# leistungsmesser_4fach.net
KiCad netlist of a schematic drawn in EAGLE
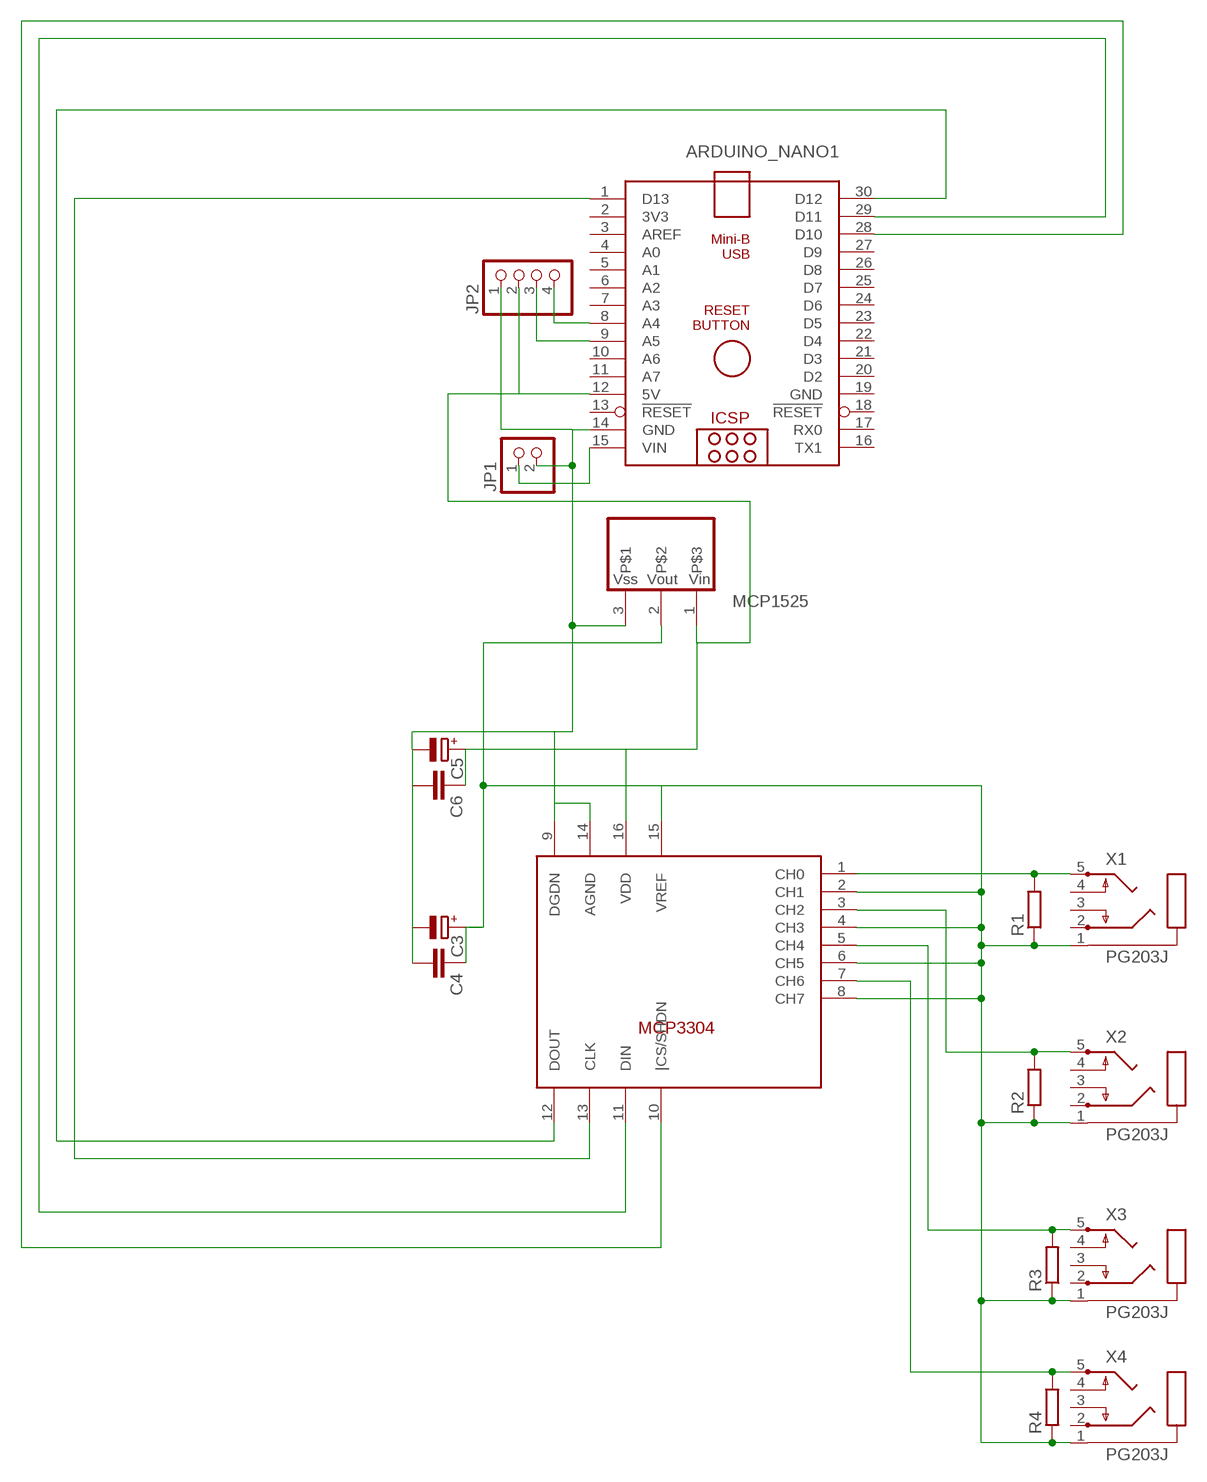
[diagram p0: schematic, sheet 1]

(export (version "E")
  (design (tool "Eeschema 10.0.6"))
  (components
    (comp (ref "ARDUINO_NANO1")
      (value "ARDUINO_NANO")
      (footprint "eagle-import:ARDUINO_NANO")
      (libsource (lib "eagle-import") (part "ARDUINO_NANO"))
    )
    (comp (ref "C3")
      (value "CPOL-EUE2,5-6E")
      (footprint "eagle-import:E2,5-6E")
      (libsource (lib "eagle-import") (part "CPOL-EUE2,5-6E"))
    )
    (comp (ref "C4")
      (value "C-EU025-024X044")
      (footprint "eagle-import:C025-024X044")
      (libsource (lib "eagle-import") (part "C-EU025-024X044"))
    )
    (comp (ref "C5")
      (value "CPOL-EUE2,5-6E")
      (footprint "eagle-import:E2,5-6E")
      (libsource (lib "eagle-import") (part "CPOL-EUE2,5-6E"))
    )
    (comp (ref "C6")
      (value "C-EU025-024X044")
      (footprint "eagle-import:C025-024X044")
      (libsource (lib "eagle-import") (part "C-EU025-024X044"))
    )
    (comp (ref "IC4")
      (value "MCP1525")
      (footprint "eagle-import:TO92-")
      (libsource (lib "eagle-import") (part "MCP1525"))
    )
    (comp (ref "JP1")
      (value "PINHD-1X2")
      (footprint "eagle-import:1X02")
      (libsource (lib "eagle-import") (part "PINHD-1X2"))
    )
    (comp (ref "JP2")
      (value "PINHD-1X4")
      (footprint "eagle-import:1X04")
      (libsource (lib "eagle-import") (part "PINHD-1X4"))
    )
    (comp (ref "R1")
      (value "R-EU_0309/V")
      (footprint "eagle-import:0309V")
      (libsource (lib "eagle-import") (part "R-EU_0309/V"))
    )
    (comp (ref "R2")
      (value "R-EU_0309/V")
      (footprint "eagle-import:0309V")
      (libsource (lib "eagle-import") (part "R-EU_0309/V"))
    )
    (comp (ref "R3")
      (value "R-EU_0309/V")
      (footprint "eagle-import:0309V")
      (libsource (lib "eagle-import") (part "R-EU_0309/V"))
    )
    (comp (ref "R4")
      (value "R-EU_0309/V")
      (footprint "eagle-import:0309V")
      (libsource (lib "eagle-import") (part "R-EU_0309/V"))
    )
    (comp (ref "U$1")
      (value "MCP3304")
      (footprint "eagle-import:DIP16")
      (libsource (lib "eagle-import") (part "MCP3304"))
    )
    (comp (ref "X1")
      (value "PG203J")
      (footprint "eagle-import:PG203J")
      (libsource (lib "eagle-import") (part "PG203J"))
    )
    (comp (ref "X2")
      (value "PG203J")
      (footprint "eagle-import:PG203J")
      (libsource (lib "eagle-import") (part "PG203J"))
    )
    (comp (ref "X3")
      (value "PG203J")
      (footprint "eagle-import:PG203J")
      (libsource (lib "eagle-import") (part "PG203J"))
    )
    (comp (ref "X4")
      (value "PG203J")
      (footprint "eagle-import:PG203J")
      (libsource (lib "eagle-import") (part "PG203J"))
    )
  )
  (nets
    (net (code "1") (name "/GND") (class "Default")
      (node (ref "ARDUINO_NANO1") (pin "19") (pinfunction "GND_19") (pintype "power_in"))
    )
    (net (code "2") (name "Net-(ARDUINO_NANO1-5V)") (class "Default")
      (node (ref "ARDUINO_NANO1") (pin "12") (pinfunction "5V_12") (pintype "power_in"))
      (node (ref "C5") (pin "+") (pinfunction "+_+") (pintype "passive"))
      (node (ref "C6") (pin "1") (pinfunction "1_1") (pintype "passive"))
      (node (ref "IC4") (pin "1") (pinfunction "P$3_1") (pintype "output"))
      (node (ref "JP2") (pin "2") (pinfunction "2_2") (pintype "passive"))
      (node (ref "U$1") (pin "16") (pinfunction "VDD_16") (pintype "bidirectional"))
    )
    (net (code "3") (name "Net-(ARDUINO_NANO1-A4)") (class "Default")
      (node (ref "ARDUINO_NANO1") (pin "8") (pinfunction "A4_8") (pintype "bidirectional"))
      (node (ref "JP2") (pin "4") (pinfunction "4_4") (pintype "passive"))
    )
    (net (code "4") (name "Net-(ARDUINO_NANO1-A5)") (class "Default")
      (node (ref "ARDUINO_NANO1") (pin "9") (pinfunction "A5_9") (pintype "bidirectional"))
      (node (ref "JP2") (pin "3") (pinfunction "3_3") (pintype "passive"))
    )
    (net (code "5") (name "Net-(ARDUINO_NANO1-D10)") (class "Default")
      (node (ref "ARDUINO_NANO1") (pin "28") (pinfunction "D10_28") (pintype "bidirectional"))
      (node (ref "U$1") (pin "10") (pinfunction "|CS/SHDN_10") (pintype "bidirectional"))
    )
    (net (code "6") (name "Net-(ARDUINO_NANO1-D11)") (class "Default")
      (node (ref "ARDUINO_NANO1") (pin "29") (pinfunction "D11_29") (pintype "bidirectional"))
      (node (ref "U$1") (pin "11") (pinfunction "DIN_11") (pintype "bidirectional"))
    )
    (net (code "7") (name "Net-(ARDUINO_NANO1-D12)") (class "Default")
      (node (ref "ARDUINO_NANO1") (pin "30") (pinfunction "D12_30") (pintype "bidirectional"))
      (node (ref "U$1") (pin "12") (pinfunction "DOUT_12") (pintype "bidirectional"))
    )
    (net (code "8") (name "Net-(ARDUINO_NANO1-D13)") (class "Default")
      (node (ref "ARDUINO_NANO1") (pin "1") (pinfunction "D13_1") (pintype "bidirectional"))
      (node (ref "U$1") (pin "13") (pinfunction "CLK_13") (pintype "bidirectional"))
    )
    (net (code "9") (name "Net-(ARDUINO_NANO1-VIN)") (class "Default")
      (node (ref "ARDUINO_NANO1") (pin "15") (pinfunction "VIN_15") (pintype "power_in"))
      (node (ref "JP1") (pin "1") (pinfunction "1_1") (pintype "passive"))
    )
    (net (code "10") (name "Net-(IC4-P$1)") (class "Default")
      (node (ref "ARDUINO_NANO1") (pin "14") (pinfunction "GND_14") (pintype "power_in"))
      (node (ref "C3") (pin "-") (pinfunction "-_-") (pintype "passive"))
      (node (ref "C4") (pin "2") (pinfunction "2_2") (pintype "passive"))
      (node (ref "C5") (pin "-") (pinfunction "-_-") (pintype "passive"))
      (node (ref "C6") (pin "2") (pinfunction "2_2") (pintype "passive"))
      (node (ref "IC4") (pin "3") (pinfunction "P$1_3") (pintype "bidirectional"))
      (node (ref "JP1") (pin "2") (pinfunction "2_2") (pintype "passive"))
      (node (ref "JP2") (pin "1") (pinfunction "1_1") (pintype "passive"))
      (node (ref "U$1") (pin "14") (pinfunction "AGND_14") (pintype "bidirectional"))
      (node (ref "U$1") (pin "9") (pinfunction "DGDN_9") (pintype "bidirectional"))
    )
    (net (code "11") (name "Net-(IC4-P$2)") (class "Default")
      (node (ref "C3") (pin "+") (pinfunction "+_+") (pintype "passive"))
      (node (ref "C4") (pin "1") (pinfunction "1_1") (pintype "passive"))
      (node (ref "IC4") (pin "2") (pinfunction "P$2_2") (pintype "bidirectional"))
      (node (ref "R1") (pin "1") (pinfunction "1_1") (pintype "passive"))
      (node (ref "R2") (pin "1") (pinfunction "1_1") (pintype "passive"))
      (node (ref "R3") (pin "1") (pinfunction "1_1") (pintype "passive"))
      (node (ref "R4") (pin "1") (pinfunction "1_1") (pintype "passive"))
      (node (ref "U$1") (pin "15") (pinfunction "VREF_15") (pintype "bidirectional"))
      (node (ref "U$1") (pin "2") (pinfunction "CH1_2") (pintype "bidirectional"))
      (node (ref "U$1") (pin "4") (pinfunction "CH3_4") (pintype "bidirectional"))
      (node (ref "U$1") (pin "6") (pinfunction "CH5_6") (pintype "bidirectional"))
      (node (ref "U$1") (pin "8") (pinfunction "CH7_8") (pintype "bidirectional"))
      (node (ref "X1") (pin "1") (pinfunction "1_1") (pintype "passive"))
      (node (ref "X2") (pin "1") (pinfunction "1_1") (pintype "passive"))
      (node (ref "X3") (pin "1") (pinfunction "1_1") (pintype "passive"))
      (node (ref "X4") (pin "1") (pinfunction "1_1") (pintype "passive"))
    )
    (net (code "12") (name "Net-(U$1-CH0)") (class "Default")
      (node (ref "R1") (pin "2") (pinfunction "2_2") (pintype "passive"))
      (node (ref "U$1") (pin "1") (pinfunction "CH0_1") (pintype "bidirectional"))
      (node (ref "X1") (pin "5") (pinfunction "5_5") (pintype "passive"))
    )
    (net (code "13") (name "Net-(U$1-CH2)") (class "Default")
      (node (ref "R2") (pin "2") (pinfunction "2_2") (pintype "passive"))
      (node (ref "U$1") (pin "3") (pinfunction "CH2_3") (pintype "bidirectional"))
      (node (ref "X2") (pin "5") (pinfunction "5_5") (pintype "passive"))
    )
    (net (code "14") (name "Net-(U$1-CH4)") (class "Default")
      (node (ref "R3") (pin "2") (pinfunction "2_2") (pintype "passive"))
      (node (ref "U$1") (pin "5") (pinfunction "CH4_5") (pintype "bidirectional"))
      (node (ref "X3") (pin "5") (pinfunction "5_5") (pintype "passive"))
    )
    (net (code "15") (name "Net-(U$1-CH6)") (class "Default")
      (node (ref "R4") (pin "2") (pinfunction "2_2") (pintype "passive"))
      (node (ref "U$1") (pin "7") (pinfunction "CH6_7") (pintype "bidirectional"))
      (node (ref "X4") (pin "5") (pinfunction "5_5") (pintype "passive"))
    )
    (net (code "16") (name "unconnected-(ARDUINO_NANO1-3V3-Pad2)") (class "Default")
      (node (ref "ARDUINO_NANO1") (pin "2") (pinfunction "3V3_2") (pintype "output"))
    )
    (net (code "17") (name "unconnected-(ARDUINO_NANO1-A0-Pad4)") (class "Default")
      (node (ref "ARDUINO_NANO1") (pin "4") (pinfunction "A0_4") (pintype "bidirectional"))
    )
    (net (code "18") (name "unconnected-(ARDUINO_NANO1-A1-Pad5)") (class "Default")
      (node (ref "ARDUINO_NANO1") (pin "5") (pinfunction "A1_5") (pintype "bidirectional"))
    )
    (net (code "19") (name "unconnected-(ARDUINO_NANO1-A2-Pad6)") (class "Default")
      (node (ref "ARDUINO_NANO1") (pin "6") (pinfunction "A2_6") (pintype "bidirectional"))
    )
    (net (code "20") (name "unconnected-(ARDUINO_NANO1-A3-Pad7)") (class "Default")
      (node (ref "ARDUINO_NANO1") (pin "7") (pinfunction "A3_7") (pintype "bidirectional"))
    )
    (net (code "21") (name "unconnected-(ARDUINO_NANO1-A6-Pad10)") (class "Default")
      (node (ref "ARDUINO_NANO1") (pin "10") (pinfunction "A6_10") (pintype "bidirectional"))
    )
    (net (code "22") (name "unconnected-(ARDUINO_NANO1-A7-Pad11)") (class "Default")
      (node (ref "ARDUINO_NANO1") (pin "11") (pinfunction "A7_11") (pintype "bidirectional"))
    )
    (net (code "23") (name "unconnected-(ARDUINO_NANO1-AREF-Pad3)") (class "Default")
      (node (ref "ARDUINO_NANO1") (pin "3") (pinfunction "AREF_3") (pintype "input"))
    )
    (net (code "24") (name "unconnected-(ARDUINO_NANO1-D2-Pad20)") (class "Default")
      (node (ref "ARDUINO_NANO1") (pin "20") (pinfunction "D2_20") (pintype "bidirectional"))
    )
    (net (code "25") (name "unconnected-(ARDUINO_NANO1-D3-Pad21)") (class "Default")
      (node (ref "ARDUINO_NANO1") (pin "21") (pinfunction "D3_21") (pintype "bidirectional"))
    )
    (net (code "26") (name "unconnected-(ARDUINO_NANO1-D4-Pad22)") (class "Default")
      (node (ref "ARDUINO_NANO1") (pin "22") (pinfunction "D4_22") (pintype "bidirectional"))
    )
    (net (code "27") (name "unconnected-(ARDUINO_NANO1-D5-Pad23)") (class "Default")
      (node (ref "ARDUINO_NANO1") (pin "23") (pinfunction "D5_23") (pintype "bidirectional"))
    )
    (net (code "28") (name "unconnected-(ARDUINO_NANO1-D6-Pad24)") (class "Default")
      (node (ref "ARDUINO_NANO1") (pin "24") (pinfunction "D6_24") (pintype "bidirectional"))
    )
    (net (code "29") (name "unconnected-(ARDUINO_NANO1-D7-Pad25)") (class "Default")
      (node (ref "ARDUINO_NANO1") (pin "25") (pinfunction "D7_25") (pintype "bidirectional"))
    )
    (net (code "30") (name "unconnected-(ARDUINO_NANO1-D8-Pad26)") (class "Default")
      (node (ref "ARDUINO_NANO1") (pin "26") (pinfunction "D8_26") (pintype "bidirectional"))
    )
    (net (code "31") (name "unconnected-(ARDUINO_NANO1-D9-Pad27)") (class "Default")
      (node (ref "ARDUINO_NANO1") (pin "27") (pinfunction "D9_27") (pintype "bidirectional"))
    )
    (net (code "32") (name "unconnected-(ARDUINO_NANO1-RX0-Pad17)") (class "Default")
      (node (ref "ARDUINO_NANO1") (pin "17") (pinfunction "RX0_17") (pintype "bidirectional"))
    )
    (net (code "33") (name "unconnected-(ARDUINO_NANO1-TX1-Pad16)") (class "Default")
      (node (ref "ARDUINO_NANO1") (pin "16") (pinfunction "TX1_16") (pintype "bidirectional"))
    )
    (net (code "34") (name "unconnected-(ARDUINO_NANO1-~{RESET}-Pad13)") (class "Default")
      (node (ref "ARDUINO_NANO1") (pin "13") (pinfunction "~{RESET}_13") (pintype "input"))
    )
    (net (code "35") (name "unconnected-(ARDUINO_NANO1-~{RESET}-Pad18)") (class "Default")
      (node (ref "ARDUINO_NANO1") (pin "18") (pinfunction "~{RESET}_18") (pintype "input"))
    )
    (net (code "36") (name "unconnected-(X1-Pad2)") (class "Default")
      (node (ref "X1") (pin "2") (pinfunction "2_2") (pintype "passive"))
    )
    (net (code "37") (name "unconnected-(X1-Pad3)") (class "Default")
      (node (ref "X1") (pin "3") (pinfunction "3_3") (pintype "passive"))
    )
    (net (code "38") (name "unconnected-(X1-Pad4)") (class "Default")
      (node (ref "X1") (pin "4") (pinfunction "4_4") (pintype "passive"))
    )
    (net (code "39") (name "unconnected-(X2-Pad2)") (class "Default")
      (node (ref "X2") (pin "2") (pinfunction "2_2") (pintype "passive"))
    )
    (net (code "40") (name "unconnected-(X2-Pad3)") (class "Default")
      (node (ref "X2") (pin "3") (pinfunction "3_3") (pintype "passive"))
    )
    (net (code "41") (name "unconnected-(X2-Pad4)") (class "Default")
      (node (ref "X2") (pin "4") (pinfunction "4_4") (pintype "passive"))
    )
    (net (code "42") (name "unconnected-(X3-Pad2)") (class "Default")
      (node (ref "X3") (pin "2") (pinfunction "2_2") (pintype "passive"))
    )
    (net (code "43") (name "unconnected-(X3-Pad3)") (class "Default")
      (node (ref "X3") (pin "3") (pinfunction "3_3") (pintype "passive"))
    )
    (net (code "44") (name "unconnected-(X3-Pad4)") (class "Default")
      (node (ref "X3") (pin "4") (pinfunction "4_4") (pintype "passive"))
    )
    (net (code "45") (name "unconnected-(X4-Pad2)") (class "Default")
      (node (ref "X4") (pin "2") (pinfunction "2_2") (pintype "passive"))
    )
    (net (code "46") (name "unconnected-(X4-Pad3)") (class "Default")
      (node (ref "X4") (pin "3") (pinfunction "3_3") (pintype "passive"))
    )
    (net (code "47") (name "unconnected-(X4-Pad4)") (class "Default")
      (node (ref "X4") (pin "4") (pinfunction "4_4") (pintype "passive"))
    )
  )
)
